# Adafruit_Radio_FeatherWing.net
KiCad netlist of a schematic drawn in EAGLE
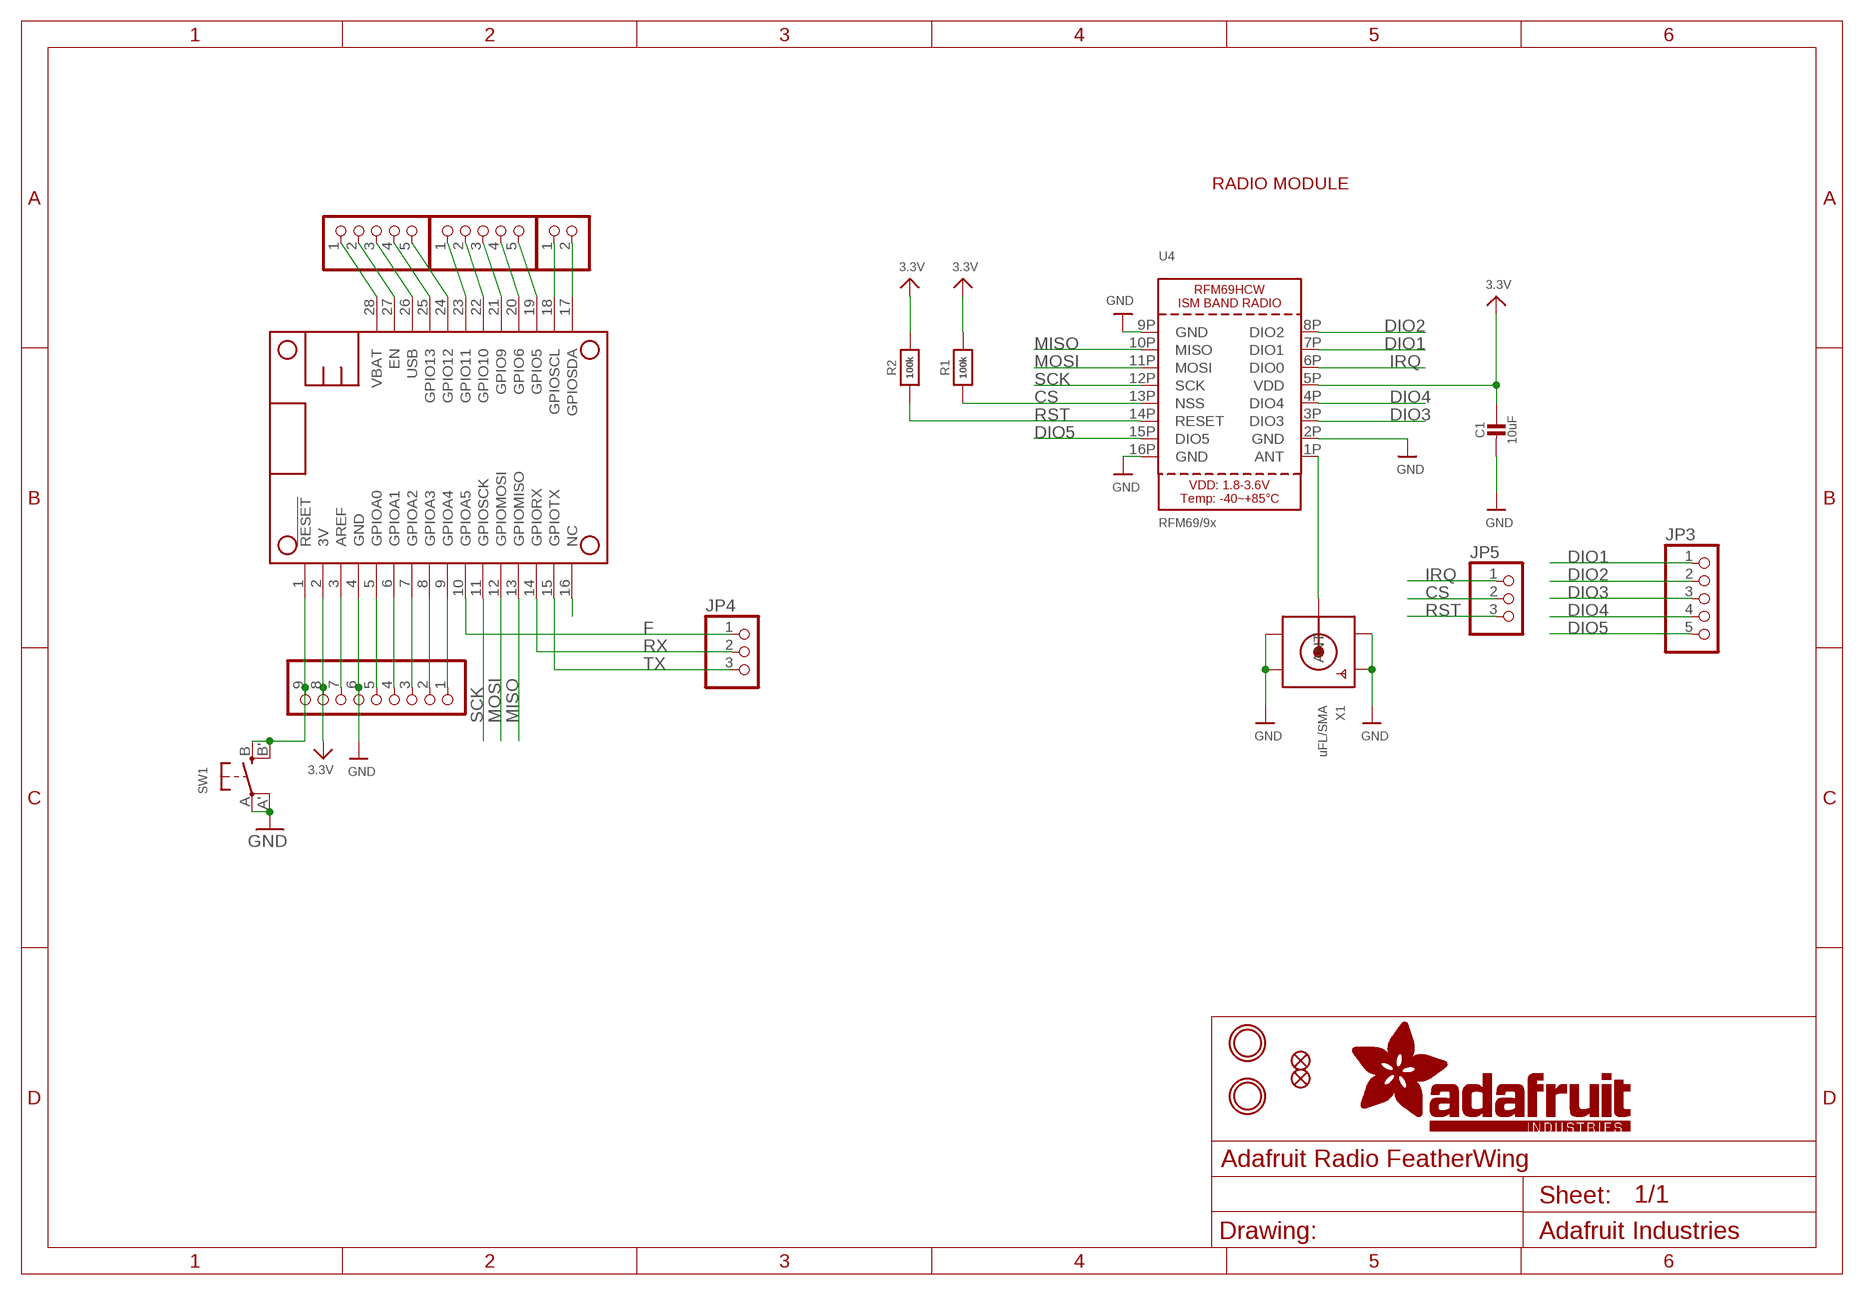
[diagram p0: schematic, sheet 1]

(export (version "E")
  (design (tool "Eeschema 10.0.6"))
  (components
    (comp (ref "C1")
      (value "10uF")
      (footprint "eagle-import:0805-NO")
      (libsource (lib "eagle-import") (part "CAP_CERAMIC0805-NOOUTLINE"))
    )
    (comp (ref "FID1")
      (value "FIDUCIAL\"\"")
      (footprint "eagle-import:FIDUCIAL_1MM")
      (libsource (lib "eagle-import") (part "FIDUCIAL{dblquote}{dblquote}"))
    )
    (comp (ref "FID2")
      (value "FIDUCIAL\"\"")
      (footprint "eagle-import:FIDUCIAL_1MM")
      (libsource (lib "eagle-import") (part "FIDUCIAL{dblquote}{dblquote}"))
    )
    (comp (ref "JP1")
      (value "HEADER-1X970MIL")
      (footprint "eagle-import:1X09_ROUND_70")
      (libsource (lib "eagle-import") (part "HEADER-1X970MIL"))
    )
    (comp (ref "JP2")
      (value "HEADER-1X570MIL")
      (footprint "eagle-import:1X05_ROUND_70")
      (libsource (lib "eagle-import") (part "HEADER-1X570MIL"))
    )
    (comp (ref "JP3")
      (value "HEADER-1X570MIL")
      (footprint "eagle-import:1X05_ROUND_70")
      (libsource (lib "eagle-import") (part "HEADER-1X570MIL"))
    )
    (comp (ref "JP4")
      (value "HEADER-1X376MIL")
      (footprint "eagle-import:1X03_ROUND_76")
      (libsource (lib "eagle-import") (part "HEADER-1X376MIL"))
    )
    (comp (ref "JP5")
      (value "HEADER-1X376MIL")
      (footprint "eagle-import:1X03_ROUND_76")
      (libsource (lib "eagle-import") (part "HEADER-1X376MIL"))
    )
    (comp (ref "JP6")
      (value "HEADER-1X2ROUND")
      (footprint "eagle-import:1X02_ROUND")
      (libsource (lib "eagle-import") (part "HEADER-1X2ROUND"))
    )
    (comp (ref "JP7")
      (value "HEADER-1X576MIL")
      (footprint "eagle-import:1X05_ROUND_76")
      (libsource (lib "eagle-import") (part "HEADER-1X576MIL"))
    )
    (comp (ref "MS1")
      (value "FEATHERWING_NOHOLES")
      (footprint "eagle-import:FEATHERWING_NOHOLES")
      (libsource (lib "eagle-import") (part "FEATHERWING_NOHOLES"))
    )
    (comp (ref "R1")
      (value "100k")
      (footprint "eagle-import:0603-NO")
      (libsource (lib "eagle-import") (part "RESISTOR_0603_NOOUT"))
    )
    (comp (ref "R2")
      (value "100k")
      (footprint "eagle-import:0603-NO")
      (libsource (lib "eagle-import") (part "RESISTOR_0603_NOOUT"))
    )
    (comp (ref "SW1")
      (value "SWITCH_TACT_SMT4.6X2.8")
      (footprint "eagle-import:BTN_KMR2_4.6X2.8")
      (libsource (lib "eagle-import") (part "SWITCH_TACT_SMT4.6X2.8"))
    )
    (comp (ref "U$7")
      (value "MOUNTINGHOLE2.5")
      (footprint "eagle-import:MOUNTINGHOLE_2.5_PLATED")
      (libsource (lib "eagle-import") (part "MOUNTINGHOLE2.5"))
    )
    (comp (ref "U$8")
      (value "MOUNTINGHOLE2.5")
      (footprint "eagle-import:MOUNTINGHOLE_2.5_PLATED")
      (libsource (lib "eagle-import") (part "MOUNTINGHOLE2.5"))
    )
    (comp (ref "U4")
      (value "RFM69/9x")
      (footprint "eagle-import:RFMHCW_SMT")
      (libsource (lib "eagle-import") (part "RFM69HCW_SMT"))
    )
    (comp (ref "X1")
      (value "uFL/SMA")
      (footprint "eagle-import:SMA_EDGELAUNCH_UFL")
      (libsource (lib "eagle-import") (part "SMACONNECTOR_EDGE_UFL"))
    )
  )
  (nets
    (net (code "1") (name "/CS") (class "Default")
      (node (ref "JP5") (pin "2") (pinfunction "2_2") (pintype "passive"))
      (node (ref "R1") (pin "1") (pinfunction "1_1") (pintype "passive"))
      (node (ref "U4") (pin "13P") (pinfunction "NSS_13P") (pintype "input"))
    )
    (net (code "2") (name "/DIO1") (class "Default")
      (node (ref "JP3") (pin "1") (pinfunction "1_1") (pintype "passive"))
      (node (ref "U4") (pin "7P") (pinfunction "DIO1_7P") (pintype "bidirectional"))
    )
    (net (code "3") (name "/DIO2") (class "Default")
      (node (ref "JP3") (pin "2") (pinfunction "2_2") (pintype "passive"))
      (node (ref "U4") (pin "8P") (pinfunction "DIO2_8P") (pintype "bidirectional"))
    )
    (net (code "4") (name "/DIO3") (class "Default")
      (node (ref "JP3") (pin "3") (pinfunction "3_3") (pintype "passive"))
      (node (ref "U4") (pin "3P") (pinfunction "DIO3_3P") (pintype "bidirectional"))
    )
    (net (code "5") (name "/DIO4") (class "Default")
      (node (ref "JP3") (pin "4") (pinfunction "4_4") (pintype "passive"))
      (node (ref "U4") (pin "4P") (pinfunction "DIO4_4P") (pintype "bidirectional"))
    )
    (net (code "6") (name "/DIO5") (class "Default")
      (node (ref "JP3") (pin "5") (pinfunction "5_5") (pintype "passive"))
      (node (ref "U4") (pin "15P") (pinfunction "DIO5_15P") (pintype "bidirectional"))
    )
    (net (code "7") (name "/F") (class "Default")
      (node (ref "JP4") (pin "1") (pinfunction "1_1") (pintype "passive"))
      (node (ref "MS1") (pin "10") (pinfunction "GPIOA5_10") (pintype "bidirectional"))
    )
    (net (code "8") (name "/IRQ") (class "Default")
      (node (ref "JP5") (pin "1") (pinfunction "1_1") (pintype "passive"))
      (node (ref "U4") (pin "6P") (pinfunction "DIO0_6P") (pintype "bidirectional"))
    )
    (net (code "9") (name "/MISO") (class "Default")
      (node (ref "MS1") (pin "13") (pinfunction "GPIOMISO_13") (pintype "bidirectional"))
      (node (ref "U4") (pin "10P") (pinfunction "MISO_10P") (pintype "output"))
    )
    (net (code "10") (name "/MOSI") (class "Default")
      (node (ref "MS1") (pin "12") (pinfunction "GPIOMOSI_12") (pintype "bidirectional"))
      (node (ref "U4") (pin "11P") (pinfunction "MOSI_11P") (pintype "input"))
    )
    (net (code "11") (name "/RST") (class "Default")
      (node (ref "JP5") (pin "3") (pinfunction "3_3") (pintype "passive"))
      (node (ref "R2") (pin "1") (pinfunction "1_1") (pintype "passive"))
      (node (ref "U4") (pin "14P") (pinfunction "RESET_14P") (pintype "input"))
    )
    (net (code "12") (name "/RX") (class "Default")
      (node (ref "JP4") (pin "2") (pinfunction "2_2") (pintype "passive"))
      (node (ref "MS1") (pin "14") (pinfunction "GPIORX_14") (pintype "bidirectional"))
    )
    (net (code "13") (name "/SCK") (class "Default")
      (node (ref "MS1") (pin "11") (pinfunction "GPIOSCK_11") (pintype "bidirectional"))
      (node (ref "U4") (pin "12P") (pinfunction "SCK_12P") (pintype "input"))
    )
    (net (code "14") (name "/TX") (class "Default")
      (node (ref "JP4") (pin "3") (pinfunction "3_3") (pintype "passive"))
      (node (ref "MS1") (pin "15") (pinfunction "GPIOTX_15") (pintype "bidirectional"))
    )
    (net (code "15") (name "3.3V") (class "Default")
      (node (ref "C1") (pin "1") (pinfunction "1_1") (pintype "passive"))
      (node (ref "JP1") (pin "8") (pinfunction "8_8") (pintype "passive"))
      (node (ref "MS1") (pin "2") (pinfunction "3V_2") (pintype "power_in"))
      (node (ref "R1") (pin "2") (pinfunction "2_2") (pintype "passive"))
      (node (ref "R2") (pin "2") (pinfunction "2_2") (pintype "passive"))
      (node (ref "U4") (pin "5P") (pinfunction "VDD_5P") (pintype "power_in"))
    )
    (net (code "16") (name "GND") (class "Default")
      (node (ref "C1") (pin "2") (pinfunction "2_2") (pintype "passive"))
      (node (ref "JP1") (pin "6") (pinfunction "6_6") (pintype "passive"))
      (node (ref "MS1") (pin "4") (pinfunction "GND_4") (pintype "power_in"))
      (node (ref "SW1") (pin "A") (pinfunction "P_A") (pintype "passive"))
      (node (ref "SW1") (pin "A'") (pinfunction "P1_A'") (pintype "passive"))
      (node (ref "U4") (pin "16P") (pinfunction "GND_16P") (pintype "power_in"))
      (node (ref "U4") (pin "2P") (pinfunction "GND_2P") (pintype "power_in"))
      (node (ref "U4") (pin "9P") (pinfunction "GND_9P") (pintype "power_in"))
      (node (ref "X1") (pin "GND@1") (pinfunction "GND1_GND@1") (pintype "power_in"))
      (node (ref "X1") (pin "GND@2") (pinfunction "GND2_GND@2") (pintype "power_in"))
      (node (ref "X1") (pin "GND@3") (pinfunction "GND3_GND@3") (pintype "power_in"))
      (node (ref "X1") (pin "GND@4") (pinfunction "GND4_GND@4") (pintype "power_in"))
    )
    (net (code "17") (name "Net-(MS1-AREF)") (class "Default")
      (node (ref "JP1") (pin "7") (pinfunction "7_7") (pintype "passive"))
      (node (ref "MS1") (pin "3") (pinfunction "AREF_3") (pintype "passive"))
    )
    (net (code "18") (name "Net-(MS1-EN)") (class "Default")
      (node (ref "JP2") (pin "2") (pinfunction "2_2") (pintype "passive"))
      (node (ref "MS1") (pin "27") (pinfunction "EN_27") (pintype "passive"))
    )
    (net (code "19") (name "Net-(MS1-GPIO5)") (class "Default")
      (node (ref "JP7") (pin "5") (pinfunction "5_5") (pintype "passive"))
      (node (ref "MS1") (pin "19") (pinfunction "GPIO5_19") (pintype "bidirectional"))
    )
    (net (code "20") (name "Net-(MS1-GPIO6)") (class "Default")
      (node (ref "JP7") (pin "4") (pinfunction "4_4") (pintype "passive"))
      (node (ref "MS1") (pin "20") (pinfunction "GPIO6_20") (pintype "bidirectional"))
    )
    (net (code "21") (name "Net-(MS1-GPIO9)") (class "Default")
      (node (ref "JP7") (pin "3") (pinfunction "3_3") (pintype "passive"))
      (node (ref "MS1") (pin "21") (pinfunction "GPIO9_21") (pintype "bidirectional"))
    )
    (net (code "22") (name "Net-(MS1-GPIO10)") (class "Default")
      (node (ref "JP7") (pin "2") (pinfunction "2_2") (pintype "passive"))
      (node (ref "MS1") (pin "22") (pinfunction "GPIO10_22") (pintype "bidirectional"))
    )
    (net (code "23") (name "Net-(MS1-GPIO11)") (class "Default")
      (node (ref "JP7") (pin "1") (pinfunction "1_1") (pintype "passive"))
      (node (ref "MS1") (pin "23") (pinfunction "GPIO11_23") (pintype "bidirectional"))
    )
    (net (code "24") (name "Net-(MS1-GPIO12)") (class "Default")
      (node (ref "JP2") (pin "5") (pinfunction "5_5") (pintype "passive"))
      (node (ref "MS1") (pin "24") (pinfunction "GPIO12_24") (pintype "bidirectional"))
    )
    (net (code "25") (name "Net-(MS1-GPIO13)") (class "Default")
      (node (ref "JP2") (pin "4") (pinfunction "4_4") (pintype "passive"))
      (node (ref "MS1") (pin "25") (pinfunction "GPIO13_25") (pintype "bidirectional"))
    )
    (net (code "26") (name "Net-(MS1-GPIOA0)") (class "Default")
      (node (ref "JP1") (pin "5") (pinfunction "5_5") (pintype "passive"))
      (node (ref "MS1") (pin "5") (pinfunction "GPIOA0_5") (pintype "bidirectional"))
    )
    (net (code "27") (name "Net-(MS1-GPIOA1)") (class "Default")
      (node (ref "JP1") (pin "4") (pinfunction "4_4") (pintype "passive"))
      (node (ref "MS1") (pin "6") (pinfunction "GPIOA1_6") (pintype "bidirectional"))
    )
    (net (code "28") (name "Net-(MS1-GPIOA2)") (class "Default")
      (node (ref "JP1") (pin "3") (pinfunction "3_3") (pintype "passive"))
      (node (ref "MS1") (pin "7") (pinfunction "GPIOA2_7") (pintype "bidirectional"))
    )
    (net (code "29") (name "Net-(MS1-GPIOA3)") (class "Default")
      (node (ref "JP1") (pin "2") (pinfunction "2_2") (pintype "passive"))
      (node (ref "MS1") (pin "8") (pinfunction "GPIOA3_8") (pintype "bidirectional"))
    )
    (net (code "30") (name "Net-(MS1-GPIOA4)") (class "Default")
      (node (ref "JP1") (pin "1") (pinfunction "1_1") (pintype "passive"))
      (node (ref "MS1") (pin "9") (pinfunction "GPIOA4_9") (pintype "bidirectional"))
    )
    (net (code "31") (name "Net-(MS1-GPIOSCL)") (class "Default")
      (node (ref "JP6") (pin "1") (pinfunction "1_1") (pintype "passive"))
      (node (ref "MS1") (pin "18") (pinfunction "GPIOSCL_18") (pintype "bidirectional"))
    )
    (net (code "32") (name "Net-(MS1-GPIOSDA)") (class "Default")
      (node (ref "JP6") (pin "2") (pinfunction "2_2") (pintype "passive"))
      (node (ref "MS1") (pin "17") (pinfunction "GPIOSDA_17") (pintype "bidirectional"))
    )
    (net (code "33") (name "Net-(MS1-USB)") (class "Default")
      (node (ref "JP2") (pin "3") (pinfunction "3_3") (pintype "passive"))
      (node (ref "MS1") (pin "26") (pinfunction "USB_26") (pintype "power_in"))
    )
    (net (code "34") (name "Net-(MS1-VBAT)") (class "Default")
      (node (ref "JP2") (pin "1") (pinfunction "1_1") (pintype "passive"))
      (node (ref "MS1") (pin "28") (pinfunction "VBAT_28") (pintype "power_in"))
    )
    (net (code "35") (name "Net-(MS1-~{RESET})") (class "Default")
      (node (ref "JP1") (pin "9") (pinfunction "9_9") (pintype "passive"))
      (node (ref "MS1") (pin "1") (pinfunction "~{RESET}_1") (pintype "input"))
      (node (ref "SW1") (pin "B") (pinfunction "S_B") (pintype "passive"))
      (node (ref "SW1") (pin "B'") (pinfunction "S1_B'") (pintype "passive"))
    )
    (net (code "36") (name "Net-(U4-ANT)") (class "Default")
      (node (ref "U4") (pin "1P") (pinfunction "ANT_1P") (pintype "bidirectional"))
      (node (ref "X1") (pin "P") (pinfunction "ANT_P") (pintype "bidirectional"))
    )
    (net (code "37") (name "unconnected-(MS1-NC-Pad16)") (class "Default")
      (node (ref "MS1") (pin "16") (pinfunction "NC_16") (pintype "passive"))
    )
  )
)
